# switch-smd-20mm-mk-1_0.net
KiCad netlist of a schematic drawn in EAGLE
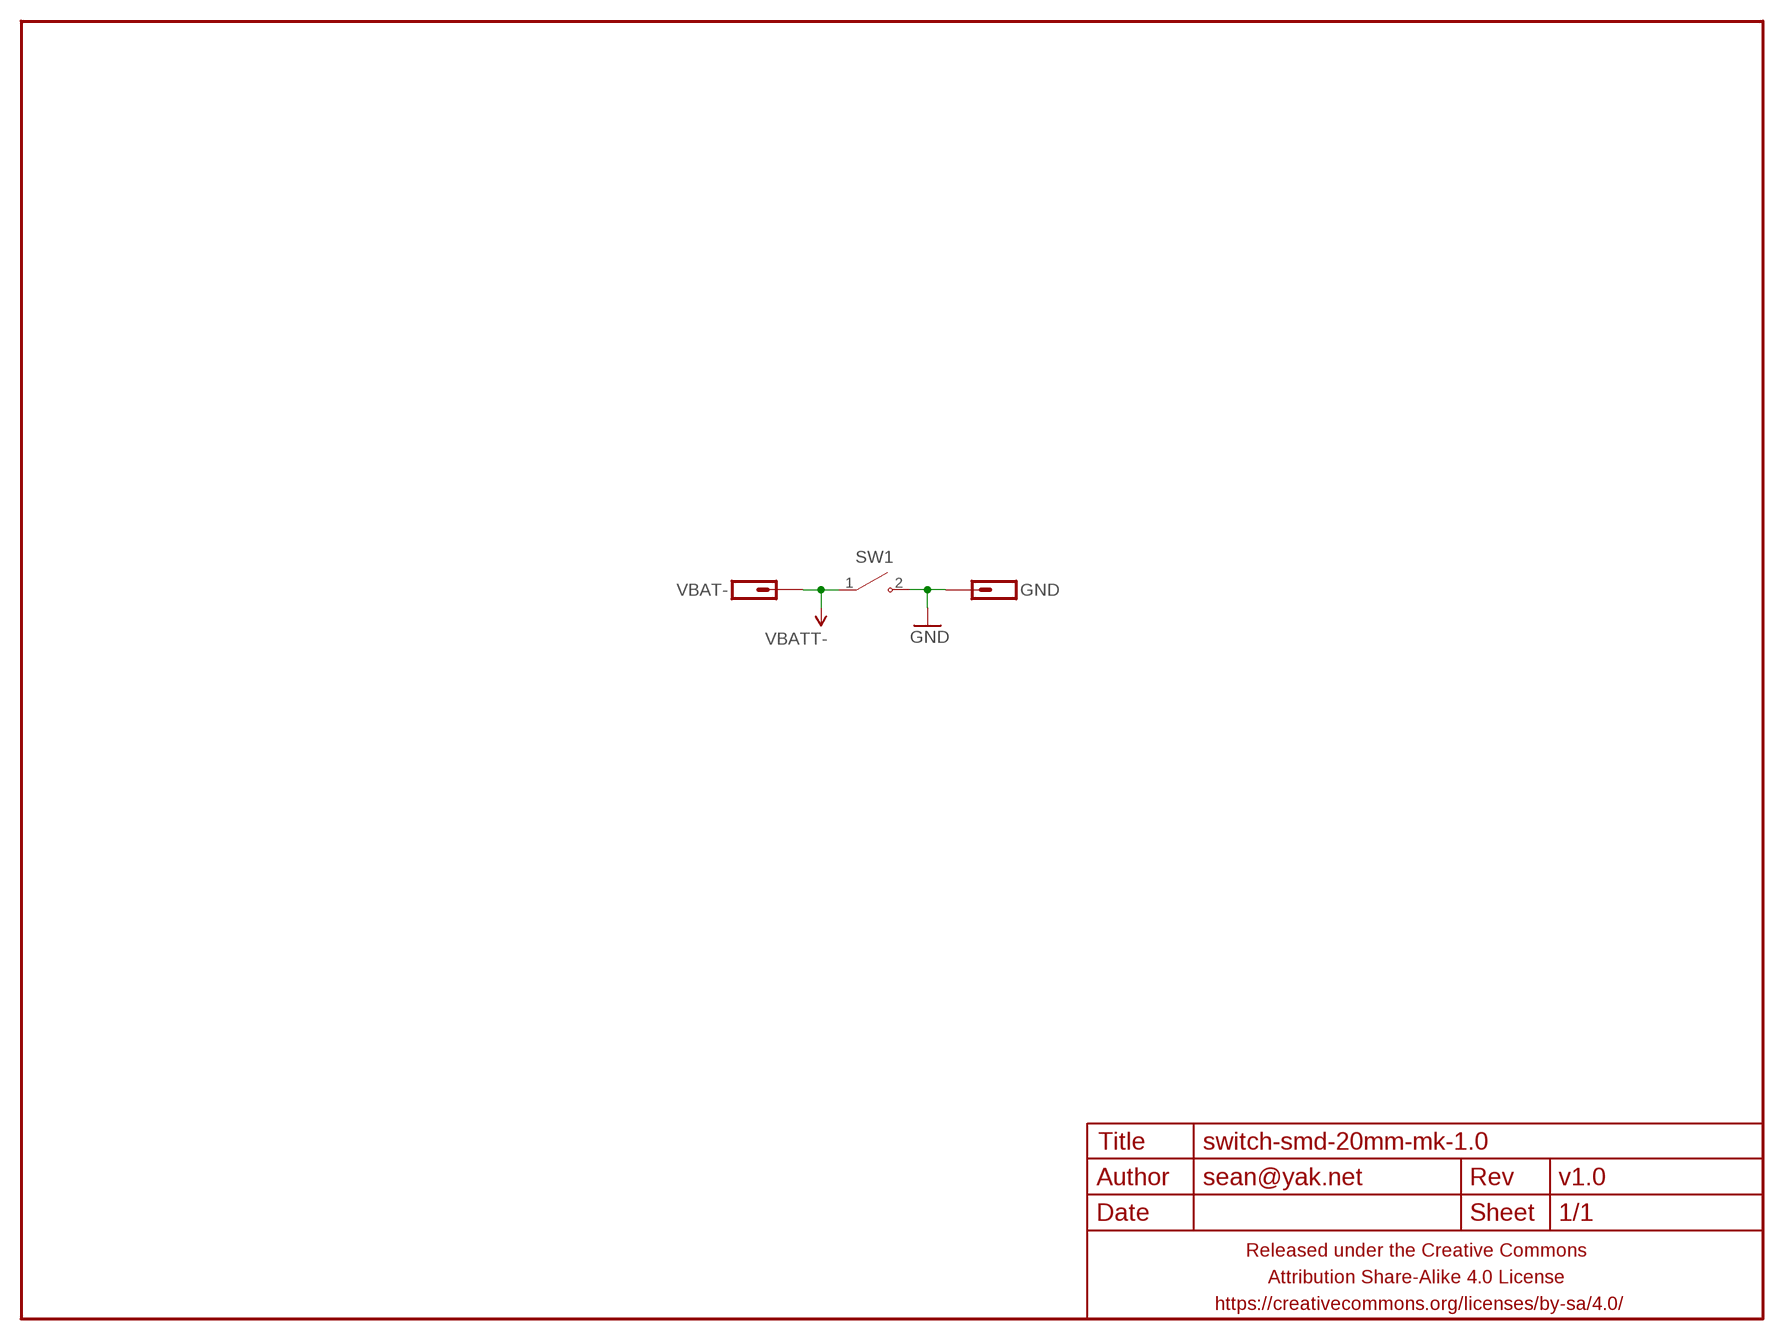
[diagram p0: schematic, sheet 1]

(export (version "E")
  (design (tool "Eeschema 10.0.6"))
  (components
    (comp (ref "FRAME1")
      (value "FRAME-LETTERNO_PACKAGE")
      (footprint "eagle-import:DUMMY")
      (fields (field (name "DESIGNER") "sean@yak.net") (field (name "VERSION") "v1.0"))
      (libsource (lib "eagle-import") (part "FRAME-LETTERNO_PACKAGE"))
    )
    (comp (ref "GND")
      (value "M01NOT-A-VIA-NOPE")
      (footprint "eagle-import:1X01_NOSILK_NOSTOP")
      (libsource (lib "eagle-import") (part "M01NOT-A-VIA-NOPE"))
    )
    (comp (ref "SW1")
      (value "SWITCH-SPSTOMTEN-1288-LESS")
      (footprint "eagle-import:OMTEN-1288-LESS")
      (libsource (lib "eagle-import") (part "SWITCH-SPSTOMTEN-1288-LESS"))
    )
    (comp (ref "VBAT-")
      (value "M01PTH-1MM-CIR-NS")
      (footprint "eagle-import:1X01-1MM-CIR-NS")
      (libsource (lib "eagle-import") (part "M01PTH-1MM-CIR-NS"))
    )
  )
  (nets
    (net (code "1") (name "GND") (class "Default")
      (node (ref "GND") (pin "P$1") (pinfunction "1_P$1") (pintype "passive"))
      (node (ref "SW1") (pin "2") (pinfunction "NO_2") (pintype "bidirectional"))
    )
    (net (code "2") (name "VBATT-") (class "Default")
      (node (ref "SW1") (pin "1") (pinfunction "COM_1") (pintype "bidirectional"))
      (node (ref "VBAT-") (pin "1") (pinfunction "1_1") (pintype "passive"))
    )
  )
)
